# USB.net
KiCad netlist of a schematic drawn in Altium Designer
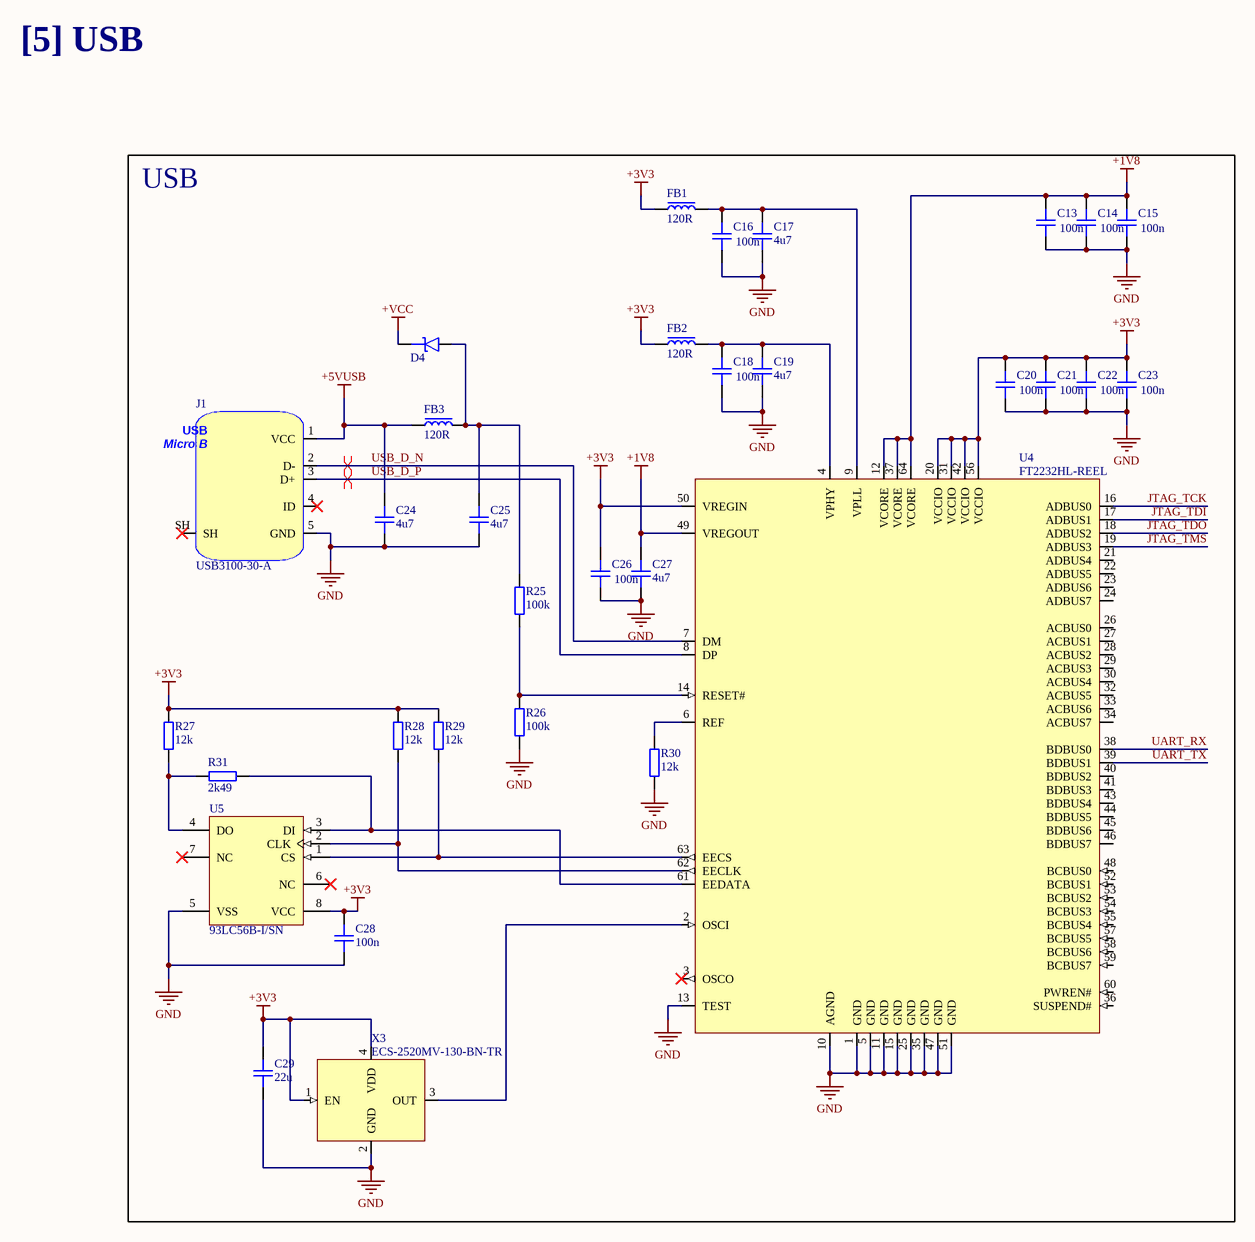
[diagram p0: USB.SchDoc]

(export (version "E")
  (design (tool "Eeschema 10.0.6"))
  (components
    (comp (ref "C13")
      (value "100n")
      (footprint "CAP_0402")
      (description "Capacitor SMD 0402")
      (libsource (lib "Schematic-Lib-PhilsLab") (part "CAP_0402"))
    )
    (comp (ref "C14")
      (value "100n")
      (footprint "CAP_0402")
      (description "Capacitor SMD 0402")
      (libsource (lib "Schematic-Lib-PhilsLab") (part "CAP_0402"))
    )
    (comp (ref "C15")
      (value "100n")
      (footprint "CAP_0402")
      (description "Capacitor SMD 0402")
      (libsource (lib "Schematic-Lib-PhilsLab") (part "CAP_0402"))
    )
    (comp (ref "C16")
      (value "100n")
      (footprint "CAP_0402")
      (description "Capacitor SMD 0402")
      (libsource (lib "Schematic-Lib-PhilsLab") (part "CAP_0402"))
    )
    (comp (ref "C17")
      (value "4u7")
      (footprint "CAP_0402")
      (description "Capacitor SMD 0402")
      (libsource (lib "Schematic-Lib-PhilsLab") (part "CAP_0402"))
    )
    (comp (ref "C18")
      (value "100n")
      (footprint "CAP_0402")
      (description "Capacitor SMD 0402")
      (libsource (lib "Schematic-Lib-PhilsLab") (part "CAP_0402"))
    )
    (comp (ref "C19")
      (value "4u7")
      (footprint "CAP_0402")
      (description "Capacitor SMD 0402")
      (libsource (lib "Schematic-Lib-PhilsLab") (part "CAP_0402"))
    )
    (comp (ref "C20")
      (value "100n")
      (footprint "CAP_0402")
      (description "Capacitor SMD 0402")
      (libsource (lib "Schematic-Lib-PhilsLab") (part "CAP_0402"))
    )
    (comp (ref "C21")
      (value "100n")
      (footprint "CAP_0402")
      (description "Capacitor SMD 0402")
      (libsource (lib "Schematic-Lib-PhilsLab") (part "CAP_0402"))
    )
    (comp (ref "C22")
      (value "100n")
      (footprint "CAP_0402")
      (description "Capacitor SMD 0402")
      (libsource (lib "Schematic-Lib-PhilsLab") (part "CAP_0402"))
    )
    (comp (ref "C23")
      (value "100n")
      (footprint "CAP_0402")
      (description "Capacitor SMD 0402")
      (libsource (lib "Schematic-Lib-PhilsLab") (part "CAP_0402"))
    )
    (comp (ref "C24")
      (value "4u7")
      (footprint "CAP_0402")
      (description "Capacitor SMD 0402")
      (libsource (lib "Schematic-Lib-PhilsLab") (part "CAP_0402"))
    )
    (comp (ref "C25")
      (value "4u7")
      (footprint "CAP_0402")
      (description "Capacitor SMD 0402")
      (libsource (lib "Schematic-Lib-PhilsLab") (part "CAP_0402"))
    )
    (comp (ref "C26")
      (value "100n")
      (footprint "CAP_0402")
      (description "Capacitor SMD 0402")
      (libsource (lib "Schematic-Lib-PhilsLab") (part "CAP_0402"))
    )
    (comp (ref "C27")
      (value "4u7")
      (footprint "CAP_0402")
      (description "Capacitor SMD 0402")
      (libsource (lib "Schematic-Lib-PhilsLab") (part "CAP_0402"))
    )
    (comp (ref "C28")
      (value "100n")
      (footprint "CAP_0402")
      (description "Capacitor SMD 0402")
      (libsource (lib "Schematic-Lib-PhilsLab") (part "CAP_0402"))
    )
    (comp (ref "C29")
      (value "22u")
      (footprint "CAP_0402")
      (description "Capacitor SMD 0402")
      (libsource (lib "Schematic-Lib-PhilsLab") (part "CAP_0402"))
    )
    (comp (ref "D4")
      (value "D_SCHOTTKY_SMC")
      (footprint "SMC-DO-214AB")
      (description "Diode Schottky SMD SMC (DO-214AB)")
      (libsource (lib "Schematic-Lib-PhilsLab") (part "D_SCHOTTKY_SMC"))
    )
    (comp (ref "FB1")
      (value "120R")
      (footprint "FB_0402")
      (description "Ferrite Bead SMD 0402")
      (libsource (lib "Schematic-Lib-PhilsLab") (part "FB_0402"))
    )
    (comp (ref "FB2")
      (value "120R")
      (footprint "FB_0402")
      (description "Ferrite Bead SMD 0402")
      (libsource (lib "Schematic-Lib-PhilsLab") (part "FB_0402"))
    )
    (comp (ref "FB3")
      (value "120R")
      (footprint "FB_0402")
      (description "Ferrite Bead SMD 0402")
      (libsource (lib "Schematic-Lib-PhilsLab") (part "FB_0402"))
    )
    (comp (ref "J1")
      (value "USB3100-30-A")
      (footprint "USB3100-30-A")
      (description "USB Connector Type Micro B 2.0 SMD Reverse Mount")
      (fields (field (name "MANUFACTURER") "GCT"))
      (libsource (lib "Schematic-Lib-PhilsLab") (part "USB3100-30-A"))
    )
    (comp (ref "R25")
      (value "100k")
      (footprint "RES_0603")
      (description "Resistor SMD 0603")
      (libsource (lib "Schematic-Lib-PhilsLab") (part "RES_0603"))
    )
    (comp (ref "R26")
      (value "100k")
      (footprint "RES_0603")
      (description "Resistor SMD 0603")
      (libsource (lib "Schematic-Lib-PhilsLab") (part "RES_0603"))
    )
    (comp (ref "R27")
      (value "12k")
      (footprint "RES_0402")
      (description "Resistor SMD 0402")
      (libsource (lib "Schematic-Lib-PhilsLab") (part "RES_0402"))
    )
    (comp (ref "R28")
      (value "12k")
      (footprint "RES_0402")
      (description "Resistor SMD 0402")
      (libsource (lib "Schematic-Lib-PhilsLab") (part "RES_0402"))
    )
    (comp (ref "R29")
      (value "12k")
      (footprint "RES_0402")
      (description "Resistor SMD 0402")
      (libsource (lib "Schematic-Lib-PhilsLab") (part "RES_0402"))
    )
    (comp (ref "R30")
      (value "12k")
      (footprint "RES_0402")
      (description "Resistor SMD 0402")
      (libsource (lib "Schematic-Lib-PhilsLab") (part "RES_0402"))
    )
    (comp (ref "R31")
      (value "2k49")
      (footprint "RES_0402")
      (description "Resistor SMD 0402")
      (libsource (lib "Schematic-Lib-PhilsLab") (part "RES_0402"))
    )
    (comp (ref "U4")
      (value "FT2232HL-REEL")
      (footprint "LQFP-64-0.5mm")
      (description "Hi-Speed Dual USB UART/FIFO IC")
      (fields (field (name "MANUFACTURER") "FTDI"))
      (libsource (lib "Schematic-Lib-PhilsLab") (part "FT2232HL-REEL"))
    )
    (comp (ref "U5")
      (value "93LC56B-I/SN")
      (footprint "SOIC-SN8_L")
      (description "2K, 128x16-bit, 2.5V Microwire Serial EEPROM, 8-Pin SOIC 150mil, Industrial Temperature")
      (libsource (lib "Altium Content Vault") (part "MEM-SEEPROM-93AA46B-P-8"))
    )
    (comp (ref "X3")
      (value "ECS-2520MV-130-BN-TR")
      (footprint "XTAL_2520")
      (fields (field (name "MANUFACTURER") "ECS"))
      (libsource (lib "Schematic-Lib-PhilsLab") (part "ECS-2520MV-130-BN-TR"))
    )
  )
  (nets
    (net (code "1") (name "+1V8") (class "Default")
      (node (ref "C13") (pin "2") (pinfunction "2_2") (pintype "passive"))
      (node (ref "C14") (pin "2") (pinfunction "2_2") (pintype "passive"))
      (node (ref "C15") (pin "2") (pinfunction "2_2") (pintype "passive"))
      (node (ref "C27") (pin "2") (pinfunction "2_2") (pintype "passive"))
      (node (ref "U4") (pin "12") (pinfunction "VCORE_12") (pintype "power_in"))
      (node (ref "U4") (pin "37") (pinfunction "VCORE_37") (pintype "power_in"))
      (node (ref "U4") (pin "49") (pinfunction "VREGOUT_49") (pintype "power_in"))
      (node (ref "U4") (pin "64") (pinfunction "VCORE_64") (pintype "power_in"))
    )
    (net (code "2") (name "+3V3") (class "Default")
      (node (ref "C20") (pin "2") (pinfunction "2_2") (pintype "passive"))
      (node (ref "C21") (pin "2") (pinfunction "2_2") (pintype "passive"))
      (node (ref "C22") (pin "2") (pinfunction "2_2") (pintype "passive"))
      (node (ref "C23") (pin "2") (pinfunction "2_2") (pintype "passive"))
      (node (ref "C26") (pin "2") (pinfunction "2_2") (pintype "passive"))
      (node (ref "C28") (pin "2") (pinfunction "2_2") (pintype "passive"))
      (node (ref "C29") (pin "2") (pinfunction "2_2") (pintype "passive"))
      (node (ref "FB1") (pin "1") (pinfunction "1_1") (pintype "passive"))
      (node (ref "FB2") (pin "1") (pinfunction "1_1") (pintype "passive"))
      (node (ref "R27") (pin "2") (pinfunction "2_2") (pintype "passive"))
      (node (ref "R28") (pin "2") (pinfunction "2_2") (pintype "passive"))
      (node (ref "R29") (pin "2") (pinfunction "2_2") (pintype "passive"))
      (node (ref "U4") (pin "20") (pinfunction "VCCIO_20") (pintype "power_in"))
      (node (ref "U4") (pin "31") (pinfunction "VCCIO_31") (pintype "power_in"))
      (node (ref "U4") (pin "42") (pinfunction "VCCIO_42") (pintype "power_in"))
      (node (ref "U4") (pin "50") (pinfunction "VREGIN_50") (pintype "power_in"))
      (node (ref "U4") (pin "56") (pinfunction "VCCIO_56") (pintype "power_in"))
      (node (ref "U5") (pin "8") (pinfunction "VCC_8") (pintype "power_in"))
      (node (ref "X3") (pin "1") (pinfunction "EN_1") (pintype "input"))
      (node (ref "X3") (pin "4") (pinfunction "VDD_4") (pintype "power_in"))
    )
    (net (code "3") (name "+5VUSB") (class "Default")
      (node (ref "C24") (pin "2") (pinfunction "2_2") (pintype "passive"))
      (node (ref "FB3") (pin "1") (pinfunction "1_1") (pintype "passive"))
      (node (ref "J1") (pin "1") (pinfunction "VCC_1") (pintype "passive"))
    )
    (net (code "4") (name "+VCC") (class "Default")
      (node (ref "D4") (pin "K") (pinfunction "K_K") (pintype "passive"))
    )
    (net (code "5") (name "/JTAG_TCK") (class "Default")
      (node (ref "U4") (pin "16") (pinfunction "ADBUS0_16") (pintype "bidirectional"))
    )
    (net (code "6") (name "/JTAG_TDI") (class "Default")
      (node (ref "U4") (pin "17") (pinfunction "ADBUS1_17") (pintype "bidirectional"))
    )
    (net (code "7") (name "/JTAG_TDO") (class "Default")
      (node (ref "U4") (pin "18") (pinfunction "ADBUS2_18") (pintype "bidirectional"))
    )
    (net (code "8") (name "/JTAG_TMS") (class "Default")
      (node (ref "U4") (pin "19") (pinfunction "ADBUS3_19") (pintype "bidirectional"))
    )
    (net (code "9") (name "/UART_RX") (class "Default")
      (node (ref "U4") (pin "38") (pinfunction "BDBUS0_38") (pintype "bidirectional"))
    )
    (net (code "10") (name "/UART_TX") (class "Default")
      (node (ref "U4") (pin "39") (pinfunction "BDBUS1_39") (pintype "bidirectional"))
    )
    (net (code "11") (name "/USB_D_N") (class "Default")
      (node (ref "J1") (pin "2") (pinfunction "D-_2") (pintype "passive"))
      (node (ref "U4") (pin "7") (pinfunction "DM_7") (pintype "bidirectional"))
    )
    (net (code "12") (name "/USB_D_P") (class "Default")
      (node (ref "J1") (pin "3") (pinfunction "D+_3") (pintype "passive"))
      (node (ref "U4") (pin "8") (pinfunction "DP_8") (pintype "bidirectional"))
    )
    (net (code "13") (name "GND") (class "Default")
      (node (ref "C13") (pin "1") (pinfunction "1_1") (pintype "passive"))
      (node (ref "C14") (pin "1") (pinfunction "1_1") (pintype "passive"))
      (node (ref "C15") (pin "1") (pinfunction "1_1") (pintype "passive"))
      (node (ref "C16") (pin "1") (pinfunction "1_1") (pintype "passive"))
      (node (ref "C17") (pin "1") (pinfunction "1_1") (pintype "passive"))
      (node (ref "C18") (pin "1") (pinfunction "1_1") (pintype "passive"))
      (node (ref "C19") (pin "1") (pinfunction "1_1") (pintype "passive"))
      (node (ref "C20") (pin "1") (pinfunction "1_1") (pintype "passive"))
      (node (ref "C21") (pin "1") (pinfunction "1_1") (pintype "passive"))
      (node (ref "C22") (pin "1") (pinfunction "1_1") (pintype "passive"))
      (node (ref "C23") (pin "1") (pinfunction "1_1") (pintype "passive"))
      (node (ref "C24") (pin "1") (pinfunction "1_1") (pintype "passive"))
      (node (ref "C25") (pin "1") (pinfunction "1_1") (pintype "passive"))
      (node (ref "C26") (pin "1") (pinfunction "1_1") (pintype "passive"))
      (node (ref "C27") (pin "1") (pinfunction "1_1") (pintype "passive"))
      (node (ref "C28") (pin "1") (pinfunction "1_1") (pintype "passive"))
      (node (ref "C29") (pin "1") (pinfunction "1_1") (pintype "passive"))
      (node (ref "J1") (pin "5") (pinfunction "GND_5") (pintype "passive"))
      (node (ref "R26") (pin "1") (pinfunction "1_1") (pintype "passive"))
      (node (ref "R30") (pin "1") (pinfunction "1_1") (pintype "passive"))
      (node (ref "U4") (pin "1") (pinfunction "GND_1") (pintype "power_in"))
      (node (ref "U4") (pin "10") (pinfunction "AGND_10") (pintype "power_in"))
      (node (ref "U4") (pin "11") (pinfunction "GND_11") (pintype "power_in"))
      (node (ref "U4") (pin "13") (pinfunction "TEST_13") (pintype "passive"))
      (node (ref "U4") (pin "15") (pinfunction "GND_15") (pintype "power_in"))
      (node (ref "U4") (pin "25") (pinfunction "GND_25") (pintype "power_in"))
      (node (ref "U4") (pin "35") (pinfunction "GND_35") (pintype "power_in"))
      (node (ref "U4") (pin "47") (pinfunction "GND_47") (pintype "power_in"))
      (node (ref "U4") (pin "5") (pinfunction "GND_5") (pintype "power_in"))
      (node (ref "U4") (pin "51") (pinfunction "GND_51") (pintype "power_in"))
      (node (ref "U5") (pin "5") (pinfunction "VSS_5") (pintype "power_in"))
      (node (ref "X3") (pin "2") (pinfunction "GND_2") (pintype "power_in"))
    )
    (net (code "14") (name "Net-(C25-Pad2)") (class "Default")
      (node (ref "C25") (pin "2") (pinfunction "2_2") (pintype "passive"))
      (node (ref "D4") (pin "A") (pinfunction "A_A") (pintype "passive"))
      (node (ref "FB3") (pin "2") (pinfunction "2_2") (pintype "passive"))
      (node (ref "R25") (pin "2") (pinfunction "2_2") (pintype "passive"))
    )
    (net (code "15") (name "Net-(U4-EECLK)") (class "Default")
      (node (ref "R28") (pin "1") (pinfunction "1_1") (pintype "passive"))
      (node (ref "U4") (pin "62") (pinfunction "EECLK_62") (pintype "output"))
      (node (ref "U5") (pin "2") (pinfunction "CLK_2") (pintype "input"))
    )
    (net (code "16") (name "Net-(U4-EECS)") (class "Default")
      (node (ref "R29") (pin "1") (pinfunction "1_1") (pintype "passive"))
      (node (ref "U4") (pin "63") (pinfunction "EECS_63") (pintype "output"))
      (node (ref "U5") (pin "1") (pinfunction "CS_1") (pintype "input"))
    )
    (net (code "17") (name "Net-(U4-EEDATA)") (class "Default")
      (node (ref "R31") (pin "1") (pinfunction "1_1") (pintype "passive"))
      (node (ref "U4") (pin "61") (pinfunction "EEDATA_61") (pintype "bidirectional"))
      (node (ref "U5") (pin "3") (pinfunction "DI_3") (pintype "input"))
    )
    (net (code "18") (name "Net-(U4-OSCI)") (class "Default")
      (node (ref "U4") (pin "2") (pinfunction "OSCI_2") (pintype "input"))
      (node (ref "X3") (pin "3") (pinfunction "OUT_3") (pintype "passive"))
    )
    (net (code "19") (name "Net-(U4-REF)") (class "Default")
      (node (ref "R30") (pin "2") (pinfunction "2_2") (pintype "passive"))
      (node (ref "U4") (pin "6") (pinfunction "REF_6") (pintype "passive"))
    )
    (net (code "20") (name "Net-(U4-RESET#)") (class "Default")
      (node (ref "R25") (pin "1") (pinfunction "1_1") (pintype "passive"))
      (node (ref "R26") (pin "2") (pinfunction "2_2") (pintype "passive"))
      (node (ref "U4") (pin "14") (pinfunction "RESET#_14") (pintype "input"))
    )
    (net (code "21") (name "Net-(U4-VPHY)") (class "Default")
      (node (ref "C18") (pin "2") (pinfunction "2_2") (pintype "passive"))
      (node (ref "C19") (pin "2") (pinfunction "2_2") (pintype "passive"))
      (node (ref "FB2") (pin "2") (pinfunction "2_2") (pintype "passive"))
      (node (ref "U4") (pin "4") (pinfunction "VPHY_4") (pintype "power_in"))
    )
    (net (code "22") (name "Net-(U4-VPLL)") (class "Default")
      (node (ref "C16") (pin "2") (pinfunction "2_2") (pintype "passive"))
      (node (ref "C17") (pin "2") (pinfunction "2_2") (pintype "passive"))
      (node (ref "FB1") (pin "2") (pinfunction "2_2") (pintype "passive"))
      (node (ref "U4") (pin "9") (pinfunction "VPLL_9") (pintype "power_in"))
    )
    (net (code "23") (name "Net-(U5-DO)") (class "Default")
      (node (ref "R27") (pin "1") (pinfunction "1_1") (pintype "passive"))
      (node (ref "R31") (pin "2") (pinfunction "2_2") (pintype "passive"))
      (node (ref "U5") (pin "4") (pinfunction "DO_4") (pintype "tri_state"))
    )
    (net (code "24") (name "unconnected-(J1-ID-Pad4)") (class "Default")
      (node (ref "J1") (pin "4") (pinfunction "ID_4") (pintype "passive+no_connect"))
    )
    (net (code "25") (name "unconnected-(J1-PadSH)") (class "Default")
      (node (ref "J1") (pin "SH") (pinfunction "SH_SH") (pintype "passive+no_connect"))
    )
    (net (code "26") (name "unconnected-(U4-ACBUS0-Pad26)") (class "Default")
      (node (ref "U4") (pin "26") (pinfunction "ACBUS0_26") (pintype "bidirectional"))
    )
    (net (code "27") (name "unconnected-(U4-ACBUS1-Pad27)") (class "Default")
      (node (ref "U4") (pin "27") (pinfunction "ACBUS1_27") (pintype "bidirectional"))
    )
    (net (code "28") (name "unconnected-(U4-ACBUS2-Pad28)") (class "Default")
      (node (ref "U4") (pin "28") (pinfunction "ACBUS2_28") (pintype "bidirectional"))
    )
    (net (code "29") (name "unconnected-(U4-ACBUS3-Pad29)") (class "Default")
      (node (ref "U4") (pin "29") (pinfunction "ACBUS3_29") (pintype "bidirectional"))
    )
    (net (code "30") (name "unconnected-(U4-ACBUS4-Pad30)") (class "Default")
      (node (ref "U4") (pin "30") (pinfunction "ACBUS4_30") (pintype "bidirectional"))
    )
    (net (code "31") (name "unconnected-(U4-ACBUS5-Pad32)") (class "Default")
      (node (ref "U4") (pin "32") (pinfunction "ACBUS5_32") (pintype "bidirectional"))
    )
    (net (code "32") (name "unconnected-(U4-ACBUS6-Pad33)") (class "Default")
      (node (ref "U4") (pin "33") (pinfunction "ACBUS6_33") (pintype "bidirectional"))
    )
    (net (code "33") (name "unconnected-(U4-ACBUS7-Pad34)") (class "Default")
      (node (ref "U4") (pin "34") (pinfunction "ACBUS7_34") (pintype "bidirectional"))
    )
    (net (code "34") (name "unconnected-(U4-ADBUS4-Pad21)") (class "Default")
      (node (ref "U4") (pin "21") (pinfunction "ADBUS4_21") (pintype "bidirectional"))
    )
    (net (code "35") (name "unconnected-(U4-ADBUS5-Pad22)") (class "Default")
      (node (ref "U4") (pin "22") (pinfunction "ADBUS5_22") (pintype "bidirectional"))
    )
    (net (code "36") (name "unconnected-(U4-ADBUS6-Pad23)") (class "Default")
      (node (ref "U4") (pin "23") (pinfunction "ADBUS6_23") (pintype "bidirectional"))
    )
    (net (code "37") (name "unconnected-(U4-ADBUS7-Pad24)") (class "Default")
      (node (ref "U4") (pin "24") (pinfunction "ADBUS7_24") (pintype "bidirectional"))
    )
    (net (code "38") (name "unconnected-(U4-BCBUS0-Pad48)") (class "Default")
      (node (ref "U4") (pin "48") (pinfunction "BCBUS0_48") (pintype "input"))
    )
    (net (code "39") (name "unconnected-(U4-BCBUS1-Pad52)") (class "Default")
      (node (ref "U4") (pin "52") (pinfunction "BCBUS1_52") (pintype "input"))
    )
    (net (code "40") (name "unconnected-(U4-BCBUS2-Pad53)") (class "Default")
      (node (ref "U4") (pin "53") (pinfunction "BCBUS2_53") (pintype "input"))
    )
    (net (code "41") (name "unconnected-(U4-BCBUS3-Pad54)") (class "Default")
      (node (ref "U4") (pin "54") (pinfunction "BCBUS3_54") (pintype "input"))
    )
    (net (code "42") (name "unconnected-(U4-BCBUS4-Pad55)") (class "Default")
      (node (ref "U4") (pin "55") (pinfunction "BCBUS4_55") (pintype "input"))
    )
    (net (code "43") (name "unconnected-(U4-BCBUS5-Pad57)") (class "Default")
      (node (ref "U4") (pin "57") (pinfunction "BCBUS5_57") (pintype "input"))
    )
    (net (code "44") (name "unconnected-(U4-BCBUS6-Pad58)") (class "Default")
      (node (ref "U4") (pin "58") (pinfunction "BCBUS6_58") (pintype "input"))
    )
    (net (code "45") (name "unconnected-(U4-BCBUS7-Pad59)") (class "Default")
      (node (ref "U4") (pin "59") (pinfunction "BCBUS7_59") (pintype "input"))
    )
    (net (code "46") (name "unconnected-(U4-BDBUS2-Pad40)") (class "Default")
      (node (ref "U4") (pin "40") (pinfunction "BDBUS2_40") (pintype "bidirectional"))
    )
    (net (code "47") (name "unconnected-(U4-BDBUS3-Pad41)") (class "Default")
      (node (ref "U4") (pin "41") (pinfunction "BDBUS3_41") (pintype "bidirectional"))
    )
    (net (code "48") (name "unconnected-(U4-BDBUS4-Pad43)") (class "Default")
      (node (ref "U4") (pin "43") (pinfunction "BDBUS4_43") (pintype "bidirectional"))
    )
    (net (code "49") (name "unconnected-(U4-BDBUS5-Pad44)") (class "Default")
      (node (ref "U4") (pin "44") (pinfunction "BDBUS5_44") (pintype "bidirectional"))
    )
    (net (code "50") (name "unconnected-(U4-BDBUS6-Pad45)") (class "Default")
      (node (ref "U4") (pin "45") (pinfunction "BDBUS6_45") (pintype "bidirectional"))
    )
    (net (code "51") (name "unconnected-(U4-BDBUS7-Pad46)") (class "Default")
      (node (ref "U4") (pin "46") (pinfunction "BDBUS7_46") (pintype "bidirectional"))
    )
    (net (code "52") (name "unconnected-(U4-OSCO-Pad3)") (class "Default")
      (node (ref "U4") (pin "3") (pinfunction "OSCO_3") (pintype "output+no_connect"))
    )
    (net (code "53") (name "unconnected-(U4-PWREN#-Pad60)") (class "Default")
      (node (ref "U4") (pin "60") (pinfunction "PWREN#_60") (pintype "input"))
    )
    (net (code "54") (name "unconnected-(U4-SUSPEND#-Pad36)") (class "Default")
      (node (ref "U4") (pin "36") (pinfunction "SUSPEND#_36") (pintype "input"))
    )
    (net (code "55") (name "unconnected-(U5-NC-Pad6)") (class "Default")
      (node (ref "U5") (pin "6") (pinfunction "NC_6") (pintype "passive+no_connect"))
    )
    (net (code "56") (name "unconnected-(U5-NC-Pad7)") (class "Default")
      (node (ref "U5") (pin "7") (pinfunction "NC_7") (pintype "passive+no_connect"))
    )
  )
)
